# placa-circuito-impresso.net
KiCad netlist of a schematic drawn in EAGLE
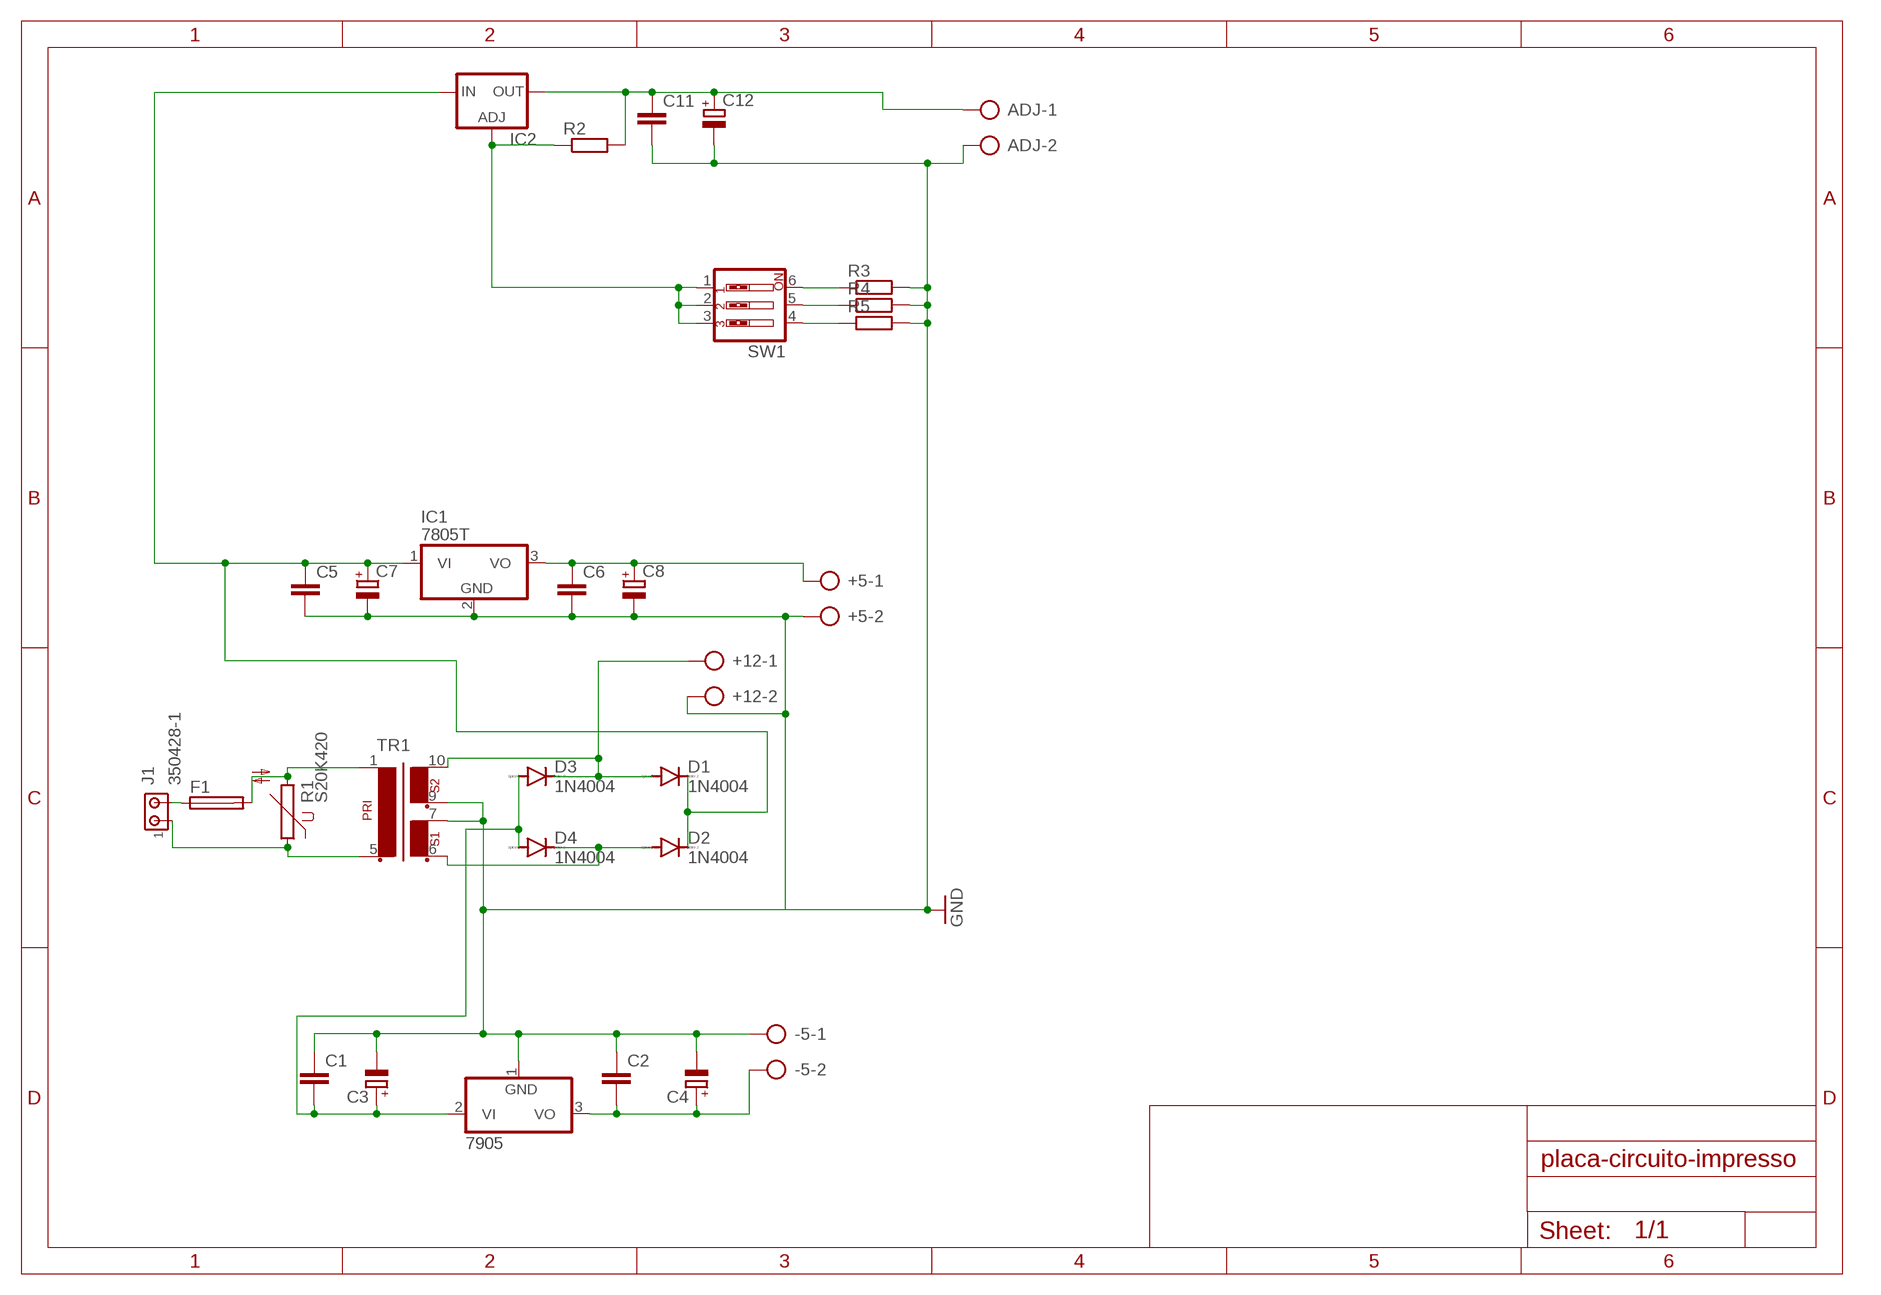
[diagram p0: schematic, sheet 1]

(export (version "E")
  (design (tool "Eeschema 10.0.6"))
  (components
    (comp (ref "+5")
      (value "AK500/2-H")
      (footprint "eagle-import:AK500_2-H")
      (libsource (lib "eagle-import") (part "AK500/2-H"))
    )
    (comp (ref "+12")
      (value "AK500/2-H")
      (footprint "eagle-import:AK500_2-H")
      (libsource (lib "eagle-import") (part "AK500/2-H"))
    )
    (comp (ref "-5")
      (value "AK500/2-H")
      (footprint "eagle-import:AK500_2-H")
      (libsource (lib "eagle-import") (part "AK500/2-H"))
    )
    (comp (ref "7905")
      (value "7905T")
      (footprint "eagle-import:TO220H")
      (libsource (lib "eagle-import") (part "79T05"))
    )
    (comp (ref "ADJ")
      (value "AK500/2-H")
      (footprint "eagle-import:AK500_2-H")
      (libsource (lib "eagle-import") (part "AK500/2-H"))
    )
    (comp (ref "C1")
      (value "C-EU025-025X050")
      (footprint "eagle-import:C025-025X050")
      (libsource (lib "eagle-import") (part "C-EU025-025X050"))
    )
    (comp (ref "C2")
      (value "C-EU025-025X050")
      (footprint "eagle-import:C025-025X050")
      (libsource (lib "eagle-import") (part "C-EU025-025X050"))
    )
    (comp (ref "C3")
      (value "CPOL-EUE2,5-6E")
      (footprint "eagle-import:E2,5-6E")
      (libsource (lib "eagle-import") (part "CPOL-EUE2,5-6E"))
    )
    (comp (ref "C4")
      (value "CPOL-EUE2,5-6E")
      (footprint "eagle-import:E2,5-6E")
      (libsource (lib "eagle-import") (part "CPOL-EUE2,5-6E"))
    )
    (comp (ref "C5")
      (value "C-EU025-025X050")
      (footprint "eagle-import:C025-025X050")
      (libsource (lib "eagle-import") (part "C-EU025-025X050"))
    )
    (comp (ref "C6")
      (value "C-EU025-025X050")
      (footprint "eagle-import:C025-025X050")
      (libsource (lib "eagle-import") (part "C-EU025-025X050"))
    )
    (comp (ref "C7")
      (value "CPOL-EUE2,5-6E")
      (footprint "eagle-import:E2,5-6E")
      (libsource (lib "eagle-import") (part "CPOL-EUE2,5-6E"))
    )
    (comp (ref "C8")
      (value "CPOL-EUE2,5-6E")
      (footprint "eagle-import:E2,5-6E")
      (libsource (lib "eagle-import") (part "CPOL-EUE2,5-6E"))
    )
    (comp (ref "C11")
      (value "C-EU025-025X050")
      (footprint "eagle-import:C025-025X050")
      (libsource (lib "eagle-import") (part "C-EU025-025X050"))
    )
    (comp (ref "C12")
      (value "CPOL-EUE2,5-6E")
      (footprint "eagle-import:E2,5-6E")
      (libsource (lib "eagle-import") (part "CPOL-EUE2,5-6E"))
    )
    (comp (ref "D1")
      (value "1N4004")
      (footprint "eagle-import:DO41-10")
      (libsource (lib "eagle-import") (part "1N4004"))
    )
    (comp (ref "D2")
      (value "1N4004")
      (footprint "eagle-import:DO41-10")
      (libsource (lib "eagle-import") (part "1N4004"))
    )
    (comp (ref "D3")
      (value "1N4004")
      (footprint "eagle-import:DO41-10")
      (libsource (lib "eagle-import") (part "1N4004"))
    )
    (comp (ref "D4")
      (value "1N4004")
      (footprint "eagle-import:DO41-10")
      (libsource (lib "eagle-import") (part "1N4004"))
    )
    (comp (ref "F1")
      (value "GSH15")
      (footprint "eagle-import:GSH15")
      (fields (field (name "MPN") "64900001039"))
      (libsource (lib "eagle-import") (part "GSH15"))
    )
    (comp (ref "IC1")
      (value "7805T")
      (footprint "eagle-import:TO220H")
      (libsource (lib "eagle-import") (part "78T05"))
    )
    (comp (ref "IC2")
      (value "LM317TL")
      (footprint "eagle-import:317TL")
      (libsource (lib "eagle-import") (part "LM317TL"))
    )
    (comp (ref "J1")
      (value "350428-1")
      (footprint "eagle-import:350428-1")
      (libsource (lib "eagle-import") (part "350428-1"))
    )
    (comp (ref "R1")
      (value "S20K420")
      (footprint "eagle-import:S20K420")
      (libsource (lib "eagle-import") (part "S20K420"))
    )
    (comp (ref "R2")
      (value "R-EU_0204/7")
      (footprint "eagle-import:0204_7")
      (libsource (lib "eagle-import") (part "R-EU_0204/7"))
    )
    (comp (ref "R3")
      (value "R-EU_0204/7")
      (footprint "eagle-import:0204_7")
      (libsource (lib "eagle-import") (part "R-EU_0204/7"))
    )
    (comp (ref "R4")
      (value "R-EU_0204/7")
      (footprint "eagle-import:0204_7")
      (libsource (lib "eagle-import") (part "R-EU_0204/7"))
    )
    (comp (ref "R5")
      (value "R-EU_0204/7")
      (footprint "eagle-import:0204_7")
      (libsource (lib "eagle-import") (part "R-EU_0204/7"))
    )
    (comp (ref "SW1")
      (value "SW_DIP-3")
      (footprint "eagle-import:EDG-03")
      (libsource (lib "eagle-import") (part "SW_DIP-3"))
    )
    (comp (ref "TR1")
      (value "EI30-2")
      (footprint "eagle-import:EI30-2")
      (libsource (lib "eagle-import") (part "EI30-2"))
    )
  )
  (nets
    (net (code "1") (name "GND") (class "Default")
      (node (ref "+12") (pin "2") (pinfunction "KL_2") (pintype "passive"))
      (node (ref "+5") (pin "2") (pinfunction "KL_2") (pintype "passive"))
      (node (ref "-5") (pin "1") (pinfunction "KL_1") (pintype "passive"))
      (node (ref "7905") (pin "1") (pinfunction "GND_1") (pintype "passive"))
      (node (ref "ADJ") (pin "2") (pinfunction "KL_2") (pintype "passive"))
      (node (ref "C1") (pin "1") (pinfunction "1_1") (pintype "passive"))
      (node (ref "C11") (pin "2") (pinfunction "2_2") (pintype "passive"))
      (node (ref "C12") (pin "-") (pinfunction "-_-") (pintype "passive"))
      (node (ref "C2") (pin "1") (pinfunction "1_1") (pintype "passive"))
      (node (ref "C3") (pin "-") (pinfunction "-_-") (pintype "passive"))
      (node (ref "C4") (pin "-") (pinfunction "-_-") (pintype "passive"))
      (node (ref "C5") (pin "2") (pinfunction "2_2") (pintype "passive"))
      (node (ref "C6") (pin "2") (pinfunction "2_2") (pintype "passive"))
      (node (ref "C7") (pin "-") (pinfunction "-_-") (pintype "passive"))
      (node (ref "C8") (pin "-") (pinfunction "-_-") (pintype "passive"))
      (node (ref "IC1") (pin "2") (pinfunction "GND_2") (pintype "passive"))
      (node (ref "R3") (pin "2") (pinfunction "2_2") (pintype "passive"))
      (node (ref "R4") (pin "2") (pinfunction "2_2") (pintype "passive"))
      (node (ref "R5") (pin "2") (pinfunction "2_2") (pintype "passive"))
      (node (ref "TR1") (pin "7") (pinfunction "4_7") (pintype "passive"))
      (node (ref "TR1") (pin "9") (pinfunction "5_9") (pintype "passive"))
    )
    (net (code "2") (name "Net-(+5A-KL)") (class "Default")
      (node (ref "+5") (pin "1") (pinfunction "KL_1") (pintype "passive"))
      (node (ref "C6") (pin "1") (pinfunction "1_1") (pintype "passive"))
      (node (ref "C8") (pin "+") (pinfunction "+_+") (pintype "passive"))
      (node (ref "IC1") (pin "3") (pinfunction "VO_3") (pintype "passive"))
    )
    (net (code "3") (name "Net-(+12A-KL)") (class "Default")
      (node (ref "+12") (pin "1") (pinfunction "KL_1") (pintype "passive"))
      (node (ref "D1") (pin "A") (pinfunction "A_A") (pintype "passive"))
      (node (ref "D3") (pin "C") (pinfunction "C_C") (pintype "passive"))
      (node (ref "TR1") (pin "10") (pinfunction "6_10") (pintype "passive"))
    )
    (net (code "4") (name "Net-(-5B-KL)") (class "Default")
      (node (ref "-5") (pin "2") (pinfunction "KL_2") (pintype "passive"))
      (node (ref "7905") (pin "3") (pinfunction "VO_3") (pintype "passive"))
      (node (ref "C2") (pin "2") (pinfunction "2_2") (pintype "passive"))
      (node (ref "C4") (pin "+") (pinfunction "+_+") (pintype "passive"))
    )
    (net (code "5") (name "Net-(7905-VI)") (class "Default")
      (node (ref "7905") (pin "2") (pinfunction "VI_2") (pintype "input"))
      (node (ref "C1") (pin "2") (pinfunction "2_2") (pintype "passive"))
      (node (ref "C3") (pin "+") (pinfunction "+_+") (pintype "passive"))
      (node (ref "D3") (pin "A") (pinfunction "A_A") (pintype "passive"))
      (node (ref "D4") (pin "A") (pinfunction "A_A") (pintype "passive"))
    )
    (net (code "6") (name "Net-(ADJA-KL)") (class "Default")
      (node (ref "ADJ") (pin "1") (pinfunction "KL_1") (pintype "passive"))
      (node (ref "C11") (pin "1") (pinfunction "1_1") (pintype "passive"))
      (node (ref "C12") (pin "+") (pinfunction "+_+") (pintype "passive"))
      (node (ref "IC2") (pin "2") (pinfunction "OUT_2") (pintype "passive"))
      (node (ref "R2") (pin "2") (pinfunction "2_2") (pintype "passive"))
    )
    (net (code "7") (name "Net-(F1-Pad1)") (class "Default")
      (node (ref "F1") (pin "1") (pinfunction "1_1") (pintype "passive"))
      (node (ref "J1") (pin "2") (pinfunction "2_2") (pintype "passive"))
    )
    (net (code "8") (name "Net-(F1-Pad2)") (class "Default")
      (node (ref "F1") (pin "2") (pinfunction "2_2") (pintype "passive"))
      (node (ref "R1") (pin "2") (pinfunction "2_2") (pintype "passive"))
      (node (ref "TR1") (pin "1") (pinfunction "1_1") (pintype "passive"))
    )
    (net (code "9") (name "Net-(IC1-VI)") (class "Default")
      (node (ref "C5") (pin "1") (pinfunction "1_1") (pintype "passive"))
      (node (ref "C7") (pin "+") (pinfunction "+_+") (pintype "passive"))
      (node (ref "D1") (pin "C") (pinfunction "C_C") (pintype "passive"))
      (node (ref "D2") (pin "C") (pinfunction "C_C") (pintype "passive"))
      (node (ref "IC1") (pin "1") (pinfunction "VI_1") (pintype "input"))
      (node (ref "IC2") (pin "3") (pinfunction "IN_3") (pintype "input"))
    )
    (net (code "10") (name "Net-(IC2-ADJ)") (class "Default")
      (node (ref "IC2") (pin "1") (pinfunction "ADJ_1") (pintype "input"))
      (node (ref "R2") (pin "1") (pinfunction "1_1") (pintype "passive"))
      (node (ref "SW1") (pin "1") (pinfunction "1_1") (pintype "passive"))
      (node (ref "SW1") (pin "2") (pinfunction "2_2") (pintype "passive"))
      (node (ref "SW1") (pin "3") (pinfunction "3_3") (pintype "passive"))
    )
    (net (code "11") (name "Net-(R3-Pad1)") (class "Default")
      (node (ref "R3") (pin "1") (pinfunction "1_1") (pintype "passive"))
      (node (ref "SW1") (pin "6") (pinfunction "6_6") (pintype "passive"))
    )
    (net (code "12") (name "Net-(R4-Pad1)") (class "Default")
      (node (ref "R4") (pin "1") (pinfunction "1_1") (pintype "passive"))
      (node (ref "SW1") (pin "5") (pinfunction "5_5") (pintype "passive"))
    )
    (net (code "13") (name "Net-(R5-Pad1)") (class "Default")
      (node (ref "R5") (pin "1") (pinfunction "1_1") (pintype "passive"))
      (node (ref "SW1") (pin "4") (pinfunction "4_4") (pintype "passive"))
    )
    (net (code "14") (name "Net-(TR1-2)") (class "Default")
      (node (ref "J1") (pin "1") (pinfunction "1_1") (pintype "passive"))
      (node (ref "R1") (pin "1") (pinfunction "1_1") (pintype "passive"))
      (node (ref "TR1") (pin "5") (pinfunction "2_5") (pintype "passive"))
    )
    (net (code "15") (name "Net-(TR1-3)") (class "Default")
      (node (ref "D2") (pin "A") (pinfunction "A_A") (pintype "passive"))
      (node (ref "D4") (pin "C") (pinfunction "C_C") (pintype "passive"))
      (node (ref "TR1") (pin "6") (pinfunction "3_6") (pintype "passive"))
    )
  )
)
